# SolderingStation_Processor.net
KiCad netlist of a schematic drawn in Altium Designer
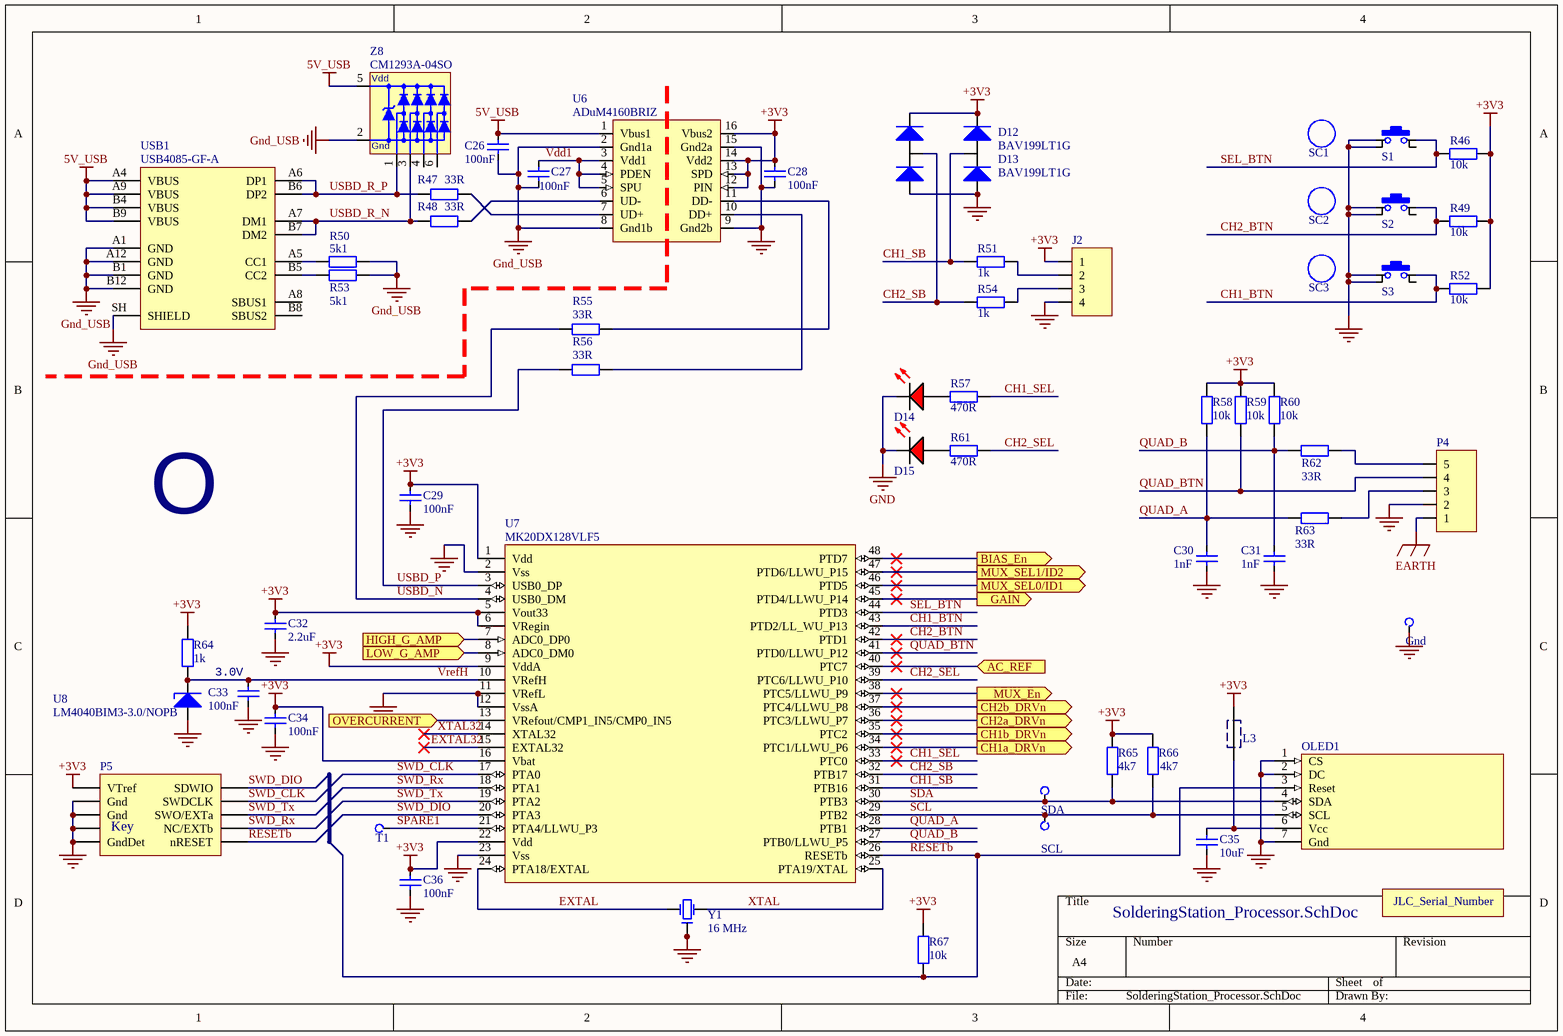
[diagram p0: SolderingStation_Processor.SchDoc]

(export (version "E")
  (design (tool "Eeschema 10.0.6"))
  (components
    (comp (ref "C26")
      (value "100nF")
      (footprint "CCNP1608-0603")
      (description "Capacitor non-polar SMT 0603")
      (fields
        (field (name "MANUFACTURER") "Generic Components")
        (field (name "PUBLISHER") "Altium Hobart Technology Centre")
      )
      (libsource (lib "MyLibrary") (part "Cap_CCNP_0603"))
    )
    (comp (ref "C27")
      (value "100nF")
      (footprint "CCNP1608-0603")
      (description "Capacitor non-polar SMT 0603")
      (fields
        (field (name "MANUFACTURER") "Generic Components")
        (field (name "PUBLISHER") "Altium Hobart Technology Centre")
      )
      (libsource (lib "MyLibrary") (part "Cap_CCNP_0603"))
    )
    (comp (ref "C28")
      (value "100nF")
      (footprint "CCNP1608-0603")
      (description "Capacitor non-polar SMT 0603")
      (fields
        (field (name "MANUFACTURER") "Generic Components")
        (field (name "PUBLISHER") "Altium Hobart Technology Centre")
      )
      (libsource (lib "MyLibrary") (part "Cap_CCNP_0603"))
    )
    (comp (ref "C29")
      (value "100nF")
      (footprint "CCNP1608-0603")
      (description "Capacitor non-polar SMT 0603")
      (fields
        (field (name "MANUFACTURER") "Generic Components")
        (field (name "PUBLISHER") "Altium Hobart Technology Centre")
      )
      (libsource (lib "MyLibrary") (part "Cap_CCNP_0603"))
    )
    (comp (ref "C30")
      (value "1nF")
      (footprint "CCNP1608-0603")
      (description "Capacitor non-polar SMT 0603")
      (fields
        (field (name "MANUFACTURER") "Generic Components")
        (field (name "PUBLISHER") "Altium Hobart Technology Centre")
      )
      (libsource (lib "MyLibrary") (part "Cap_CCNP_0603"))
    )
    (comp (ref "C31")
      (value "1nF")
      (footprint "CCNP1608-0603")
      (description "Capacitor non-polar SMT 0603")
      (fields
        (field (name "MANUFACTURER") "Generic Components")
        (field (name "PUBLISHER") "Altium Hobart Technology Centre")
      )
      (libsource (lib "MyLibrary") (part "Cap_CCNP_0603"))
    )
    (comp (ref "C32")
      (value "2.2uF")
      (footprint "CCNP1608-0603")
      (description "Capacitor")
      (fields
        (field (name "MANUFACTURER") "Generic Components")
        (field (name "PUBLISHER") "Altium Hobart Technology Centre")
      )
      (libsource (lib "MyLibrary") (part "Cap"))
    )
    (comp (ref "C33")
      (value "100nF")
      (footprint "CCNP1608-0603")
      (description "Capacitor non-polar SMT 0603")
      (fields
        (field (name "MANUFACTURER") "Generic Components")
        (field (name "PUBLISHER") "Altium Hobart Technology Centre")
      )
      (libsource (lib "MyLibrary") (part "Cap_CCNP_0603"))
    )
    (comp (ref "C34")
      (value "100nF")
      (footprint "CCNP1608-0603")
      (description "Capacitor non-polar SMT 0603")
      (fields
        (field (name "MANUFACTURER") "Generic Components")
        (field (name "PUBLISHER") "Altium Hobart Technology Centre")
      )
      (libsource (lib "MyLibrary") (part "Cap_CCNP_0603"))
    )
    (comp (ref "C35")
      (value "10uF")
      (footprint "CCNP2012-0805")
      (description "Capacitor")
      (fields
        (field (name "MANUFACTURER") "Generic Components")
        (field (name "PUBLISHER") "Altium Hobart Technology Centre")
      )
      (libsource (lib "MyLibrary") (part "Cap"))
    )
    (comp (ref "C36")
      (value "100nF")
      (footprint "CCNP1608-0603")
      (description "Capacitor non-polar SMT 0603")
      (fields
        (field (name "MANUFACTURER") "Generic Components")
        (field (name "PUBLISHER") "Altium Hobart Technology Centre")
      )
      (libsource (lib "MyLibrary") (part "Cap_CCNP_0603"))
    )
    (comp (ref "D12")
      (value "BAV199LT1G")
      (footprint "SOT23_M")
      (description "Dual Series low-leakage switching diodes, 3-Pin SOT-23")
      (libsource (lib "MySchLib") (part "BAV199LT1G"))
    )
    (comp (ref "D13")
      (value "BAV199LT1G")
      (footprint "SOT23_M")
      (description "Dual Series low-leakage switching diodes, 3-Pin SOT-23")
      (libsource (lib "MySchLib") (part "BAV199LT1G"))
    )
    (comp (ref "D14")
      (value "LED")
      (footprint "LED3MM-RED - 10mm Proud")
      (description "3mm Red LED")
      (fields (field (name "MANUFACTURER") "Generic Components") (field (name "PUBLISHER") "Altium Limited"))
      (libsource (lib "MySchLib") (part "LED_3MM_RED"))
    )
    (comp (ref "D15")
      (value "LED")
      (footprint "LED3MM-RED - 10mm Proud")
      (description "3mm Red LED")
      (fields (field (name "MANUFACTURER") "Generic Components") (field (name "PUBLISHER") "Altium Limited"))
      (libsource (lib "MySchLib") (part "LED_3MM_RED"))
    )
    (comp (ref "Gnd")
      (value "Gnd")
      (footprint "PCBPIN - 0.7mm")
      (description "Test Point")
      (libsource (lib "MySchLib") (part "TP"))
    )
    (comp (ref "J2")
      (value "JST XH Connector, 4-Pin")
      (footprint "jst-b4b-xh-ax")
      (fields (field (name "PUBLISHER") "Altium Limited"))
      (libsource (lib "MyLibrary") (part "JST-B4B-XH-A"))
    )
    (comp (ref "JLC_Serial_Number1")
      (value "JLC_Serial_Number")
      (footprint "JLC_Serial_Number")
      (libsource (lib "MyLibrary") (part "JLC_Serial_Number"))
    )
    (comp (ref "L3")
      (value "Ferrite Bead")
      (footprint "FB2012-0805")
      (description "Ferrite Bead SMT 0805, TDK MPZ2012S102AT, 0.15OHM, 1.5A")
      (libsource (lib "MySchLib") (part "Ferrite Bead 0805"))
    )
    (comp (ref "Logo1")
      (value "OSHW Logo")
      (footprint "OSHW")
      (libsource (lib "MyLibrary") (part "OSHW Logo"))
    )
    (comp (ref "OLED1")
      (value "OLED_Display")
      (footprint "OLED_Display_128x64_2.4inch - no mounting holes")
      (description "OLED Display 128x64 pixels, 2.4inch")
      (libsource (lib "MySchLib") (part "OLED_Display_128x64_2.4inch"))
    )
    (comp (ref "P4")
      (value "Header, 5-Pin")
      (footprint "HDR1X5S")
      (fields (field (name "PUBLISHER") "Altium Limited"))
      (libsource (lib "MyLibrary") (part "Header 1x5"))
    )
    (comp (ref "P5")
      (value "SWD Connector 2x5-Pin")
      (footprint "SWD-2x5-Jig-Header")
      (fields (field (name "PUBLISHER") "Altium Limited"))
      (libsource (lib "MySchLib") (part "SWD2X5_JIG"))
    )
    (comp (ref "R46")
      (value "10k")
      (footprint "CR1608-0603_N")
      (description "Resistor SMT 0603")
      (fields
        (field (name "MANUFACTURER") "Generic Components")
        (field (name "PUBLISHER") "Altium Hobart Technology Centre")
      )
      (libsource (lib "") (part "Res_CR0603_2"))
    )
    (comp (ref "R47")
      (value "33R")
      (footprint "CR1608-0603_N")
      (description "Resistor SMT 0603")
      (fields
        (field (name "MANUFACTURER") "Generic Components")
        (field (name "PUBLISHER") "Altium Hobart Technology Centre")
      )
      (libsource (lib "") (part "Res_CR0603_1"))
    )
    (comp (ref "R48")
      (value "33R")
      (footprint "CR1608-0603_N")
      (description "Resistor SMT 0603")
      (fields
        (field (name "MANUFACTURER") "Generic Components")
        (field (name "PUBLISHER") "Altium Hobart Technology Centre")
      )
      (libsource (lib "") (part "Res_CR0603_1"))
    )
    (comp (ref "R49")
      (value "10k")
      (footprint "CR1608-0603_N")
      (description "Resistor SMT 0603")
      (fields
        (field (name "MANUFACTURER") "Generic Components")
        (field (name "PUBLISHER") "Altium Hobart Technology Centre")
      )
      (libsource (lib "") (part "Res_CR0603_2"))
    )
    (comp (ref "R50")
      (value "5k1")
      (footprint "CR1608-0603_N")
      (description "Resistor SMT 0603")
      (fields
        (field (name "MANUFACTURER") "Generic Components")
        (field (name "PUBLISHER") "Altium Hobart Technology Centre")
      )
      (libsource (lib "") (part "Res_CR0603_2"))
    )
    (comp (ref "R51")
      (value "1k")
      (footprint "CR1608-0603_N")
      (description "Resistor SMT 0603")
      (fields
        (field (name "MANUFACTURER") "Generic Components")
        (field (name "PUBLISHER") "Altium Hobart Technology Centre")
      )
      (libsource (lib "MyLibrary") (part "Res_CR0603"))
    )
    (comp (ref "R52")
      (value "10k")
      (footprint "CR1608-0603_N")
      (description "Resistor SMT 0603")
      (fields
        (field (name "MANUFACTURER") "Generic Components")
        (field (name "PUBLISHER") "Altium Hobart Technology Centre")
      )
      (libsource (lib "") (part "Res_CR0603_2"))
    )
    (comp (ref "R53")
      (value "5k1")
      (footprint "CR1608-0603_N")
      (description "Resistor SMT 0603")
      (fields
        (field (name "MANUFACTURER") "Generic Components")
        (field (name "PUBLISHER") "Altium Hobart Technology Centre")
      )
      (libsource (lib "") (part "Res_CR0603_2"))
    )
    (comp (ref "R54")
      (value "1k")
      (footprint "CR1608-0603_N")
      (description "Resistor SMT 0603")
      (fields
        (field (name "MANUFACTURER") "Generic Components")
        (field (name "PUBLISHER") "Altium Hobart Technology Centre")
      )
      (libsource (lib "MyLibrary") (part "Res_CR0603"))
    )
    (comp (ref "R55")
      (value "33R")
      (footprint "CR1608-0603_N")
      (description "Resistor SMT 0603")
      (fields
        (field (name "MANUFACTURER") "Generic Components")
        (field (name "PUBLISHER") "Altium Hobart Technology Centre")
      )
      (libsource (lib "") (part "Res_CR0603_1"))
    )
    (comp (ref "R56")
      (value "33R")
      (footprint "CR1608-0603_N")
      (description "Resistor SMT 0603")
      (fields
        (field (name "MANUFACTURER") "Generic Components")
        (field (name "PUBLISHER") "Altium Hobart Technology Centre")
      )
      (libsource (lib "") (part "Res_CR0603_1"))
    )
    (comp (ref "R57")
      (value "470R")
      (footprint "CR1608-0603_N")
      (description "Resistor SMT 0603")
      (fields
        (field (name "MANUFACTURER") "Generic Components")
        (field (name "PUBLISHER") "Altium Hobart Technology Centre")
      )
      (libsource (lib "") (part "Res_CR0603_1"))
    )
    (comp (ref "R58")
      (value "10k")
      (footprint "CR1608-0603_N")
      (description "Resistor SMT 0603")
      (fields
        (field (name "MANUFACTURER") "Generic Components")
        (field (name "PUBLISHER") "Altium Hobart Technology Centre")
      )
      (libsource (lib "MyLibrary") (part "Res_CR0603"))
    )
    (comp (ref "R59")
      (value "10k")
      (footprint "CR1608-0603_N")
      (description "Resistor SMT 0603")
      (fields
        (field (name "MANUFACTURER") "Generic Components")
        (field (name "PUBLISHER") "Altium Hobart Technology Centre")
      )
      (libsource (lib "MyLibrary") (part "Res_CR0603"))
    )
    (comp (ref "R60")
      (value "10k")
      (footprint "CR1608-0603_N")
      (description "Resistor SMT 0603")
      (fields
        (field (name "MANUFACTURER") "Generic Components")
        (field (name "PUBLISHER") "Altium Hobart Technology Centre")
      )
      (libsource (lib "MyLibrary") (part "Res_CR0603"))
    )
    (comp (ref "R61")
      (value "470R")
      (footprint "CR1608-0603_N")
      (description "Resistor SMT 0603")
      (fields
        (field (name "MANUFACTURER") "Generic Components")
        (field (name "PUBLISHER") "Altium Hobart Technology Centre")
      )
      (libsource (lib "MyLibrary") (part "Res_CR0603"))
    )
    (comp (ref "R62")
      (value "33R")
      (footprint "CR1608-0603_N")
      (description "Resistor SMT 0603")
      (fields
        (field (name "MANUFACTURER") "Generic Components")
        (field (name "PUBLISHER") "Altium Hobart Technology Centre")
      )
      (libsource (lib "") (part "Res_CR0603_1"))
    )
    (comp (ref "R63")
      (value "33R")
      (footprint "CR1608-0603_N")
      (description "Resistor SMT 0603")
      (fields
        (field (name "MANUFACTURER") "Generic Components")
        (field (name "PUBLISHER") "Altium Hobart Technology Centre")
      )
      (libsource (lib "") (part "Res_CR0603_1"))
    )
    (comp (ref "R64")
      (value "1k")
      (footprint "CR1608-0603_N")
      (description "Resistor SMT 0603")
      (fields
        (field (name "MANUFACTURER") "Generic Components")
        (field (name "PUBLISHER") "Altium Hobart Technology Centre")
      )
      (libsource (lib "") (part "Res_CR0603_1"))
    )
    (comp (ref "R65")
      (value "4k7")
      (footprint "CR1608-0603_N")
      (description "Resistor SMT 0603")
      (fields
        (field (name "MANUFACTURER") "Generic Components")
        (field (name "PUBLISHER") "Altium Hobart Technology Centre")
      )
      (libsource (lib "MyLibrary") (part "Res_CR0603"))
    )
    (comp (ref "R66")
      (value "4k7")
      (footprint "CR1608-0603_N")
      (description "Resistor SMT 0603")
      (fields
        (field (name "MANUFACTURER") "Generic Components")
        (field (name "PUBLISHER") "Altium Hobart Technology Centre")
      )
      (libsource (lib "MyLibrary") (part "Res_CR0603"))
    )
    (comp (ref "R67")
      (value "10k")
      (footprint "CR1608-0603_N")
      (description "Resistor SMT 0603")
      (fields
        (field (name "MANUFACTURER") "Generic Components")
        (field (name "PUBLISHER") "Altium Hobart Technology Centre")
      )
      (libsource (lib "MyLibrary") (part "Res_CR0603"))
    )
    (comp (ref "S1")
      (value "SW_PB-B3F1052")
      (footprint "SW_MIN_PB-B3F1052")
      (description "Switch miniature push-button")
      (fields (field (name "MANUFACTURER") "Generic Components") (field (name "PUBLISHER") "Altium Limited"))
      (libsource (lib "MySchLib") (part "SW_PB-B3F1052"))
    )
    (comp (ref "S2")
      (value "SW_PB-B3F1052")
      (footprint "SW_MIN_PB-B3F1052")
      (description "Switch miniature push-button")
      (fields (field (name "MANUFACTURER") "Generic Components") (field (name "PUBLISHER") "Altium Limited"))
      (libsource (lib "MySchLib") (part "SW_PB-B3F1052"))
    )
    (comp (ref "S3")
      (value "SW_PB-B3F1052")
      (footprint "SW_MIN_PB-B3F1052")
      (description "Switch miniature push-button")
      (fields (field (name "MANUFACTURER") "Generic Components") (field (name "PUBLISHER") "Altium Limited"))
      (libsource (lib "MySchLib") (part "SW_PB-B3F1052"))
    )
    (comp (ref "SC1")
      (value "B32-2010")
      (footprint "SW-CAP-B32-2010")
      (description "Switch Cap")
      (libsource (lib "MySchLib") (part "Switch-Cap - B32-2010"))
    )
    (comp (ref "SC2")
      (value "B32-2010")
      (footprint "SW-CAP-B32-2010")
      (description "Switch Cap")
      (libsource (lib "MySchLib") (part "Switch-Cap - B32-2010"))
    )
    (comp (ref "SC3")
      (value "B32-2010")
      (footprint "SW-CAP-B32-2010")
      (description "Switch Cap")
      (libsource (lib "MySchLib") (part "Switch-Cap - B32-2010"))
    )
    (comp (ref "SCL")
      (value "SCL")
      (footprint "PCBPIN - 0.7mm")
      (description "Test Point")
      (libsource (lib "MySchLib") (part "TP"))
    )
    (comp (ref "SDA")
      (value "SDA")
      (footprint "PCBPIN - 0.7mm")
      (description "Test Point")
      (libsource (lib "MySchLib") (part "TP"))
    )
    (comp (ref "T1")
      (value "PTA4")
      (footprint "PCBPIN - 0.7mm")
      (description "Test Point")
      (libsource (lib "MySchLib") (part "TP"))
    )
    (comp (ref "U6")
      (value "ADuM4160BRIZ")
      (footprint "SOIC127P1030-16M")
      (description "Full/Low Speed 5 kV USB Digital Isolator")
      (libsource (lib "MySchLib") (part "ADuM4160BRIZ"))
    )
    (comp (ref "U7")
      (value "MK20DX128VLF5")
      (footprint "TSQFP50P900X900-48M")
      (description "Kinetis K20: 50MHz Cortex-M4 Performance MCU, 160KB Flash, 16KB SRAM, Full-Speed USB, 48-LQFP")
      (libsource (lib "MySchLib") (part "MK20DX128VLF5"))
    )
    (comp (ref "U8")
      (value "LM4040BIM3-3.0/NOPB")
      (footprint "SOT23_M")
      (description "IC 2.5V VREF SHUNT 0.2% SOT23-3")
      (libsource (lib "MySchLib") (part "LM4040BIM3-2.5/NOPB"))
    )
    (comp (ref "USB1")
      (value "USB4085-GF-A")
      (footprint "USB4085-GF-A")
      (description "USB-C, USB 2.0 Receptacle Connector 16 Position Through Hole, Right Angle")
      (fields (field (name "DIGIKEY PART NUMBER") "2073-USB4085-GF-ACT-ND"))
      (libsource (lib "MyLibrary") (part "USB4085-GF-A"))
    )
    (comp (ref "Y1")
      (value "16 MHz")
      (footprint "Crystal_SMD_3.2x2.5")
      (description "Crystal SMD 3.2 x 2.5 x 0.7 mm")
      (fields
        (field (name "MANUFACTURER") "Generic Components")
        (field (name "PUBLISHER") "Altium Hobart Technology Centre")
      )
      (libsource (lib "MyLibrary") (part "Crystal 16MHz"))
    )
    (comp (ref "Z8")
      (value "CM1293A-04SO")
      (footprint "SOT457_M - 180")
      (description "Ultra low capacitance quadruple rail-to-rail ESD protection")
      (libsource (lib "MySchLib") (part "CM1293A-04SO"))
    )
  )
  (nets
    (net (code "1") (name "+3V3") (class "Default")
      (node (ref "C28") (pin "2") (pinfunction "2_2") (pintype "passive"))
      (node (ref "C29") (pin "2") (pinfunction "2_2") (pintype "passive"))
      (node (ref "C32") (pin "2") (pinfunction "2_2") (pintype "passive"))
      (node (ref "C34") (pin "2") (pinfunction "2_2") (pintype "passive"))
      (node (ref "C36") (pin "2") (pinfunction "2_2") (pintype "passive"))
      (node (ref "D12") (pin "2") (pinfunction "A2_2") (pintype "passive"))
      (node (ref "D13") (pin "2") (pinfunction "A2_2") (pintype "passive"))
      (node (ref "J2") (pin "1") (pinfunction "1_1") (pintype "passive"))
      (node (ref "L3") (pin "1") (pinfunction "1_1") (pintype "passive"))
      (node (ref "P5") (pin "1") (pinfunction "VTref_1") (pintype "passive"))
      (node (ref "R46") (pin "2") (pinfunction "2_2") (pintype "passive"))
      (node (ref "R49") (pin "2") (pinfunction "2_2") (pintype "passive"))
      (node (ref "R52") (pin "2") (pinfunction "2_2") (pintype "passive"))
      (node (ref "R58") (pin "2") (pinfunction "2_2") (pintype "passive"))
      (node (ref "R59") (pin "2") (pinfunction "2_2") (pintype "passive"))
      (node (ref "R60") (pin "2") (pinfunction "2_2") (pintype "passive"))
      (node (ref "R64") (pin "1") (pinfunction "1_1") (pintype "passive"))
      (node (ref "R65") (pin "2") (pinfunction "2_2") (pintype "passive"))
      (node (ref "R66") (pin "2") (pinfunction "2_2") (pintype "passive"))
      (node (ref "R67") (pin "2") (pinfunction "2_2") (pintype "passive"))
      (node (ref "U6") (pin "12") (pinfunction "PIN_12") (pintype "input"))
      (node (ref "U6") (pin "13") (pinfunction "SPD_13") (pintype "input"))
      (node (ref "U6") (pin "14") (pinfunction "Vdd2_14") (pintype "power_in"))
      (node (ref "U6") (pin "16") (pinfunction "Vbus2_16") (pintype "power_in"))
      (node (ref "U7") (pin "1") (pinfunction "Vdd_1") (pintype "power_in"))
      (node (ref "U7") (pin "16") (pinfunction "Vbat_16") (pintype "passive"))
      (node (ref "U7") (pin "22") (pinfunction "Vdd_22") (pintype "power_in"))
      (node (ref "U7") (pin "5") (pinfunction "Vout33_5") (pintype "power_in"))
      (node (ref "U7") (pin "6") (pinfunction "VRegin_6") (pintype "passive"))
      (node (ref "U7") (pin "9") (pinfunction "VddA_9") (pintype "power_in"))
    )
    (net (code "2") (name "/AC_REF") (class "Default")
      (node (ref "U7") (pin "40") (pinfunction "PTC7_40") (pintype "bidirectional"))
    )
    (net (code "3") (name "/BIAS_En") (class "Default")
      (node (ref "U7") (pin "48") (pinfunction "PTD7_48") (pintype "bidirectional"))
    )
    (net (code "4") (name "/CH1_BTN") (class "Default")
      (node (ref "R52") (pin "1") (pinfunction "1_1") (pintype "passive"))
      (node (ref "S3") (pin "2") (pinfunction "2_2") (pintype "passive"))
      (node (ref "U7") (pin "43") (pinfunction "PTD2/LL_WU_P13_43") (pintype "bidirectional"))
    )
    (net (code "5") (name "/CH1_SB") (class "Default")
      (node (ref "D13") (pin "3") (pinfunction "K_3") (pintype "passive"))
      (node (ref "R51") (pin "1") (pinfunction "1_1") (pintype "passive"))
      (node (ref "U7") (pin "31") (pinfunction "PTB16_31") (pintype "bidirectional"))
    )
    (net (code "6") (name "/CH1_SEL") (class "Default")
      (node (ref "R57") (pin "1") (pinfunction "1_1") (pintype "passive"))
      (node (ref "U7") (pin "33") (pinfunction "PTC0_33") (pintype "bidirectional"))
    )
    (net (code "7") (name "/CH1a_DRVn") (class "Default")
      (node (ref "U7") (pin "34") (pinfunction "PTC1/LLWU_P6_34") (pintype "bidirectional"))
    )
    (net (code "8") (name "/CH1b_DRVn") (class "Default")
      (node (ref "U7") (pin "35") (pinfunction "PTC2_35") (pintype "bidirectional"))
    )
    (net (code "9") (name "/CH2_BTN") (class "Default")
      (node (ref "R49") (pin "1") (pinfunction "1_1") (pintype "passive"))
      (node (ref "S2") (pin "2") (pinfunction "2_2") (pintype "passive"))
      (node (ref "U7") (pin "42") (pinfunction "PTD1_42") (pintype "bidirectional"))
    )
    (net (code "10") (name "/CH2_SB") (class "Default")
      (node (ref "D12") (pin "3") (pinfunction "K_3") (pintype "passive"))
      (node (ref "R54") (pin "1") (pinfunction "1_1") (pintype "passive"))
      (node (ref "U7") (pin "32") (pinfunction "PTB17_32") (pintype "bidirectional"))
    )
    (net (code "11") (name "/CH2_SEL") (class "Default")
      (node (ref "R61") (pin "2") (pinfunction "2_2") (pintype "passive"))
      (node (ref "U7") (pin "39") (pinfunction "PTC6/LLWU_P10_39") (pintype "bidirectional"))
    )
    (net (code "12") (name "/CH2a_DRVn") (class "Default")
      (node (ref "U7") (pin "36") (pinfunction "PTC3/LLWU_P7_36") (pintype "bidirectional"))
    )
    (net (code "13") (name "/CH2b_DRVn") (class "Default")
      (node (ref "U7") (pin "37") (pinfunction "PTC4/LLWU_P8_37") (pintype "bidirectional"))
    )
    (net (code "14") (name "/EXTAL") (class "Default")
      (node (ref "U7") (pin "24") (pinfunction "PTA18/EXTAL_24") (pintype "bidirectional"))
      (node (ref "Y1") (pin "3") (pinfunction "OSC2_3") (pintype "passive"))
    )
    (net (code "15") (name "/EXTAL32") (class "Default")
      (node (ref "U7") (pin "15") (pinfunction "EXTAL32_15") (pintype "passive+no_connect"))
    )
    (net (code "16") (name "/GAIN") (class "Default")
      (node (ref "U7") (pin "45") (pinfunction "PTD4/LLWU_P14_45") (pintype "bidirectional"))
    )
    (net (code "17") (name "/HIGH_G_AMP") (class "Default")
      (node (ref "U7") (pin "7") (pinfunction "ADC0_DP0_7") (pintype "input"))
    )
    (net (code "18") (name "/LOW_G_AMP") (class "Default")
      (node (ref "U7") (pin "8") (pinfunction "ADC0_DM0_8") (pintype "input"))
    )
    (net (code "19") (name "/MUX_En") (class "Default")
      (node (ref "U7") (pin "38") (pinfunction "PTC5/LLWU_P9_38") (pintype "bidirectional"))
    )
    (net (code "20") (name "/MUX_SEL0{slash}ID1") (class "Default")
      (node (ref "U7") (pin "46") (pinfunction "PTD5_46") (pintype "bidirectional"))
    )
    (net (code "21") (name "/MUX_SEL1{slash}ID2") (class "Default")
      (node (ref "U7") (pin "47") (pinfunction "PTD6/LLWU_P15_47") (pintype "bidirectional"))
    )
    (net (code "22") (name "/OVERCURRENT") (class "Default")
      (node (ref "U7") (pin "13") (pinfunction "VRefout/CMP1_IN5/CMP0_IN5_13") (pintype "passive"))
    )
    (net (code "23") (name "/QUAD_A") (class "Default")
      (node (ref "C30") (pin "2") (pinfunction "2_2") (pintype "passive"))
      (node (ref "R58") (pin "1") (pinfunction "1_1") (pintype "passive"))
      (node (ref "R63") (pin "2") (pinfunction "2_2") (pintype "passive"))
      (node (ref "U7") (pin "28") (pinfunction "PTB1_28") (pintype "bidirectional"))
    )
    (net (code "24") (name "/QUAD_B") (class "Default")
      (node (ref "C31") (pin "2") (pinfunction "2_2") (pintype "passive"))
      (node (ref "R60") (pin "1") (pinfunction "1_1") (pintype "passive"))
      (node (ref "R62") (pin "2") (pinfunction "2_2") (pintype "passive"))
      (node (ref "U7") (pin "27") (pinfunction "PTB0/LLWU_P5_27") (pintype "bidirectional"))
    )
    (net (code "25") (name "/QUAD_BTN") (class "Default")
      (node (ref "P4") (pin "4") (pinfunction "4_4") (pintype "passive"))
      (node (ref "R59") (pin "1") (pinfunction "1_1") (pintype "passive"))
      (node (ref "U7") (pin "41") (pinfunction "PTD0/LLWU_P12_41") (pintype "bidirectional"))
    )
    (net (code "26") (name "/RESETb") (class "Default")
      (node (ref "OLED1") (pin "3") (pinfunction "Reset_3") (pintype "input"))
      (node (ref "P5") (pin "10") (pinfunction "nRESET_10") (pintype "passive"))
      (node (ref "R67") (pin "1") (pinfunction "1_1") (pintype "passive"))
      (node (ref "U7") (pin "26") (pinfunction "RESETb_26") (pintype "bidirectional"))
    )
    (net (code "27") (name "/SCL") (class "Default")
      (node (ref "OLED1") (pin "5") (pinfunction "SCL_5") (pintype "bidirectional"))
      (node (ref "R66") (pin "1") (pinfunction "1_1") (pintype "passive"))
      (node (ref "SCL") (pin "1") (pinfunction "TP_1") (pintype "passive"))
      (node (ref "U7") (pin "29") (pinfunction "PTB2_29") (pintype "bidirectional"))
    )
    (net (code "28") (name "/SDA") (class "Default")
      (node (ref "OLED1") (pin "4") (pinfunction "SDA_4") (pintype "bidirectional"))
      (node (ref "R65") (pin "1") (pinfunction "1_1") (pintype "passive"))
      (node (ref "SDA") (pin "1") (pinfunction "TP_1") (pintype "passive"))
      (node (ref "U7") (pin "30") (pinfunction "PTB3_30") (pintype "bidirectional"))
    )
    (net (code "29") (name "/SEL_BTN") (class "Default")
      (node (ref "R46") (pin "1") (pinfunction "1_1") (pintype "passive"))
      (node (ref "S1") (pin "2") (pinfunction "2_2") (pintype "passive"))
      (node (ref "U7") (pin "44") (pinfunction "PTD3_44") (pintype "bidirectional"))
    )
    (net (code "30") (name "/SPARE1") (class "Default")
      (node (ref "T1") (pin "1") (pinfunction "TP_1") (pintype "passive"))
      (node (ref "U7") (pin "21") (pinfunction "PTA4/LLWU_P3_21") (pintype "bidirectional"))
    )
    (net (code "31") (name "/SWD_CLK") (class "Default")
      (node (ref "P5") (pin "4") (pinfunction "SWDCLK_4") (pintype "passive"))
      (node (ref "U7") (pin "17") (pinfunction "PTA0_17") (pintype "bidirectional"))
    )
    (net (code "32") (name "/SWD_DIO") (class "Default")
      (node (ref "P5") (pin "2") (pinfunction "SDWIO_2") (pintype "passive"))
      (node (ref "U7") (pin "20") (pinfunction "PTA3_20") (pintype "bidirectional"))
    )
    (net (code "33") (name "/SWD_Rx") (class "Default")
      (node (ref "P5") (pin "8") (pinfunction "NC/EXTb_8") (pintype "passive"))
      (node (ref "U7") (pin "18") (pinfunction "PTA1_18") (pintype "bidirectional"))
    )
    (net (code "34") (name "/SWD_Tx") (class "Default")
      (node (ref "P5") (pin "6") (pinfunction "SWO/EXTa_6") (pintype "passive"))
      (node (ref "U7") (pin "19") (pinfunction "PTA2_19") (pintype "bidirectional"))
    )
    (net (code "35") (name "/USBD_N") (class "Default")
      (node (ref "R55") (pin "2") (pinfunction "2_2") (pintype "passive"))
      (node (ref "U7") (pin "4") (pinfunction "USB0_DM_4") (pintype "bidirectional"))
    )
    (net (code "36") (name "/USBD_P") (class "Default")
      (node (ref "R56") (pin "2") (pinfunction "2_2") (pintype "passive"))
      (node (ref "U7") (pin "3") (pinfunction "USB0_DP_3") (pintype "bidirectional"))
    )
    (net (code "37") (name "/USBD_R_N") (class "Default")
      (node (ref "R48") (pin "2") (pinfunction "2_2") (pintype "passive"))
      (node (ref "USB1") (pin "A7") (pinfunction "DM1_A7") (pintype "passive"))
      (node (ref "USB1") (pin "B7") (pinfunction "DM2_B7") (pintype "passive"))
      (node (ref "Z8") (pin "3") (pintype "passive"))
    )
    (net (code "38") (name "/USBD_R_P") (class "Default")
      (node (ref "R47") (pin "2") (pinfunction "2_2") (pintype "passive"))
      (node (ref "USB1") (pin "A6") (pinfunction "DP1_A6") (pintype "passive"))
      (node (ref "USB1") (pin "B6") (pinfunction "DP2_B6") (pintype "passive"))
      (node (ref "Z8") (pin "1") (pintype "passive"))
    )
    (net (code "39") (name "/Vdd1") (class "Default")
      (node (ref "C27") (pin "2") (pinfunction "2_2") (pintype "passive"))
      (node (ref "U6") (pin "3") (pinfunction "Vdd1_3") (pintype "power_in"))
      (node (ref "U6") (pin "4") (pinfunction "PDEN_4") (pintype "input"))
      (node (ref "U6") (pin "5") (pinfunction "SPU_5") (pintype "input"))
    )
    (net (code "40") (name "/VrefH") (class "Default")
      (node (ref "C33") (pin "2") (pinfunction "2_2") (pintype "passive"))
      (node (ref "R64") (pin "2") (pinfunction "2_2") (pintype "passive"))
      (node (ref "U7") (pin "10") (pinfunction "VRefH_10") (pintype "passive"))
      (node (ref "U8") (pin "1") (pinfunction "K_1") (pintype "passive"))
    )
    (net (code "41") (name "/XTAL") (class "Default")
      (node (ref "U7") (pin "25") (pinfunction "PTA19/XTAL_25") (pintype "bidirectional"))
      (node (ref "Y1") (pin "1") (pinfunction "OSC1_1") (pintype "passive"))
    )
    (net (code "42") (name "/XTAL32") (class "Default")
      (node (ref "U7") (pin "14") (pinfunction "XTAL32_14") (pintype "passive+no_connect"))
    )
    (net (code "43") (name "5V_USB") (class "Default")
      (node (ref "C26") (pin "2") (pinfunction "2_2") (pintype "passive"))
      (node (ref "U6") (pin "1") (pinfunction "Vbus1_1") (pintype "power_in"))
      (node (ref "USB1") (pin "A4") (pinfunction "VBUS_A4") (pintype "passive"))
      (node (ref "USB1") (pin "A9") (pinfunction "VBUS_A9") (pintype "passive"))
      (node (ref "USB1") (pin "B4") (pinfunction "VBUS_B4") (pintype "passive"))
      (node (ref "USB1") (pin "B9") (pinfunction "VBUS_B9") (pintype "passive"))
      (node (ref "Z8") (pin "5") (pinfunction "Vp_5") (pintype "passive"))
    )
    (net (code "44") (name "EARTH") (class "Default")
      (node (ref "P4") (pin "1") (pinfunction "1_1") (pintype "passive"))
    )
    (net (code "45") (name "GND") (class "Default")
      (node (ref "C28") (pin "1") (pinfunction "1_1") (pintype "passive"))
      (node (ref "C29") (pin "1") (pinfunction "1_1") (pintype "passive"))
      (node (ref "C30") (pin "1") (pinfunction "1_1") (pintype "passive"))
      (node (ref "C31") (pin "1") (pinfunction "1_1") (pintype "passive"))
      (node (ref "C32") (pin "1") (pinfunction "1_1") (pintype "passive"))
      (node (ref "C33") (pin "1") (pinfunction "1_1") (pintype "passive"))
      (node (ref "C34") (pin "1") (pinfunction "1_1") (pintype "passive"))
      (node (ref "C35") (pin "1") (pinfunction "1_1") (pintype "passive"))
      (node (ref "C36") (pin "1") (pinfunction "1_1") (pintype "passive"))
      (node (ref "D12") (pin "1") (pinfunction "A1_1") (pintype "passive"))
      (node (ref "D13") (pin "1") (pinfunction "A1_1") (pintype "passive"))
      (node (ref "D14") (pin "K") (pinfunction "K_K") (pintype "passive"))
      (node (ref "D15") (pin "K") (pinfunction "K_K") (pintype "passive"))
      (node (ref "Gnd") (pin "1") (pinfunction "TP_1") (pintype "passive"))
      (node (ref "J2") (pin "4") (pinfunction "4_4") (pintype "passive"))
      (node (ref "OLED1") (pin "1") (pinfunction "CS_1") (pintype "input"))
      (node (ref "OLED1") (pin "2") (pinfunction "DC_2") (pintype "input"))
      (node (ref "OLED1") (pin "7") (pinfunction "Gnd_7") (pintype "power_in"))
      (node (ref "P4") (pin "2") (pinfunction "2_2") (pintype "passive"))
      (node (ref "P5") (pin "0") (pinfunction "Pins_0") (pintype "power_in"))
      (node (ref "P5") (pin "3") (pinfunction "Gnd_3") (pintype "passive"))
      (node (ref "P5") (pin "5") (pinfunction "Gnd_5") (pintype "passive"))
      (node (ref "P5") (pin "9") (pinfunction "GndDet_9") (pintype "passive"))
      (node (ref "S1") (pin "1") (pinfunction "1_1") (pintype "passive"))
      (node (ref "S1") (pin "1b") (pinfunction "1b_1b") (pintype "passive"))
      (node (ref "S2") (pin "1") (pinfunction "1_1") (pintype "passive"))
      (node (ref "S2") (pin "1b") (pinfunction "1b_1b") (pintype "passive"))
      (node (ref "S3") (pin "1") (pinfunction "1_1") (pintype "passive"))
      (node (ref "S3") (pin "1b") (pinfunction "1b_1b") (pintype "passive"))
      (node (ref "U6") (pin "15") (pinfunction "Gnd2a_15") (pintype "power_in"))
      (node (ref "U6") (pin "9") (pinfunction "Gnd2b_9") (pintype "power_in"))
      (node (ref "U7") (pin "11") (pinfunction "VRefL_11") (pintype "passive"))
      (node (ref "U7") (pin "12") (pinfunction "VssA_12") (pintype "power_in"))
      (node (ref "U7") (pin "2") (pinfunction "Vss_2") (pintype "power_in"))
      (node (ref "U7") (pin "23") (pinfunction "Vss_23") (pintype "power_in"))
      (node (ref "U8") (pin "2") (pinfunction "A_2") (pintype "passive"))
      (node (ref "Y1") (pin "2") (pinfunction "Gnd_2") (pintype "passive"))
      (node (ref "Y1") (pin "4") (pinfunction "Gnd_4") (pintype "passive"))
    )
    (net (code "46") (name "Gnd_USB") (class "Default")
      (node (ref "C26") (pin "1") (pinfunction "1_1") (pintype "passive"))
      (node (ref "C27") (pin "1") (pinfunction "1_1") (pintype "passive"))
      (node (ref "R50") (pin "2") (pinfunction "2_2") (pintype "passive"))
      (node (ref "R53") (pin "2") (pinfunction "2_2") (pintype "passive"))
      (node (ref "U6") (pin "2") (pinfunction "Gnd1a_2") (pintype "power_in"))
      (node (ref "U6") (pin "8") (pinfunction "Gnd1b_8") (pintype "power_in"))
      (node (ref "USB1") (pin "A1") (pinfunction "GND_A1") (pintype "passive"))
      (node (ref "USB1") (pin "A12") (pinfunction "GND_A12") (pintype "passive"))
      (node (ref "USB1") (pin "B1") (pinfunction "GND_B1") (pintype "passive"))
      (node (ref "USB1") (pin "B12") (pinfunction "GND_B12") (pintype "passive"))
      (node (ref "USB1") (pin "SH") (pinfunction "SHIELD_SH") (pintype "passive"))
      (node (ref "Z8") (pin "2") (pinfunction "Vn_2") (pintype "passive"))
    )
    (net (code "47") (name "Net-(D14-PadA)") (class "Default")
      (node (ref "D14") (pin "A") (pinfunction "A_A") (pintype "passive"))
      (node (ref "R57") (pin "2") (pinfunction "2_2") (pintype "passive"))
    )
    (net (code "48") (name "Net-(D15-PadA)") (class "Default")
      (node (ref "D15") (pin "A") (pinfunction "A_A") (pintype "passive"))
      (node (ref "R61") (pin "1") (pinfunction "1_1") (pintype "passive"))
    )
    (net (code "49") (name "Net-(J2-Pad2)") (class "Default")
      (node (ref "J2") (pin "2") (pinfunction "2_2") (pintype "passive"))
      (node (ref "R51") (pin "2") (pinfunction "2_2") (pintype "passive"))
    )
    (net (code "50") (name "Net-(J2-Pad3)") (class "Default")
      (node (ref "J2") (pin "3") (pinfunction "3_3") (pintype "passive"))
      (node (ref "R54") (pin "2") (pinfunction "2_2") (pintype "passive"))
    )
    (net (code "51") (name "Net-(OLED1-Vcc)") (class "Default")
      (node (ref "C35") (pin "2") (pinfunction "2_2") (pintype "passive"))
      (node (ref "L3") (pin "2") (pinfunction "2_2") (pintype "passive"))
      (node (ref "OLED1") (pin "6") (pinfunction "Vcc_6") (pintype "power_in"))
    )
    (net (code "52") (name "Net-(P4-Pad3)") (class "Default")
      (node (ref "P4") (pin "3") (pinfunction "3_3") (pintype "passive"))
      (node (ref "R63") (pin "1") (pinfunction "1_1") (pintype "passive"))
    )
    (net (code "53") (name "Net-(P4-Pad5)") (class "Default")
      (node (ref "P4") (pin "5") (pinfunction "5_5") (pintype "passive"))
      (node (ref "R62") (pin "1") (pinfunction "1_1") (pintype "passive"))
    )
    (net (code "54") (name "Net-(U6-DD+)") (class "Default")
      (node (ref "R56") (pin "1") (pinfunction "1_1") (pintype "passive"))
      (node (ref "U6") (pin "10") (pinfunction "DD+_10") (pintype "bidirectional"))
    )
    (net (code "55") (name "Net-(U6-DD-)") (class "Default")
      (node (ref "R55") (pin "1") (pinfunction "1_1") (pintype "passive"))
      (node (ref "U6") (pin "11") (pinfunction "DD-_11") (pintype "bidirectional"))
    )
    (net (code "56") (name "Net-(U6-UD+)") (class "Default")
      (node (ref "R47") (pin "1") (pinfunction "1_1") (pintype "passive"))
      (node (ref "U6") (pin "7") (pinfunction "UD+_7") (pintype "bidirectional"))
    )
    (net (code "57") (name "Net-(U6-UD-)") (class "Default")
      (node (ref "R48") (pin "1") (pinfunction "1_1") (pintype "passive"))
      (node (ref "U6") (pin "6") (pinfunction "UD-_6") (pintype "bidirectional"))
    )
    (net (code "58") (name "Net-(USB1-CC1)") (class "Default")
      (node (ref "R50") (pin "1") (pinfunction "1_1") (pintype "passive"))
      (node (ref "USB1") (pin "A5") (pinfunction "CC1_A5") (pintype "passive"))
    )
    (net (code "59") (name "Net-(USB1-CC2)") (class "Default")
      (node (ref "R53") (pin "1") (pinfunction "1_1") (pintype "passive"))
      (node (ref "USB1") (pin "B5") (pinfunction "CC2_B5") (pintype "passive"))
    )
    (net (code "60") (name "unconnected-(S1-Pad2b)") (class "Default")
      (node (ref "S1") (pin "2b") (pinfunction "2b_2b") (pintype "passive"))
    )
    (net (code "61") (name "unconnected-(S2-Pad2b)") (class "Default")
      (node (ref "S2") (pin "2b") (pinfunction "2b_2b") (pintype "passive"))
    )
    (net (code "62") (name "unconnected-(S3-Pad2b)") (class "Default")
      (node (ref "S3") (pin "2b") (pinfunction "2b_2b") (pintype "passive"))
    )
    (net (code "63") (name "unconnected-(U8-NC-Pad3)") (class "Default")
      (node (ref "U8") (pin "3") (pinfunction "NC_3") (pintype "passive"))
    )
    (net (code "64") (name "unconnected-(USB1-SBUS1-PadA8)") (class "Default")
      (node (ref "USB1") (pin "A8") (pinfunction "SBUS1_A8") (pintype "passive"))
    )
    (net (code "65") (name "unconnected-(USB1-SBUS2-PadB8)") (class "Default")
      (node (ref "USB1") (pin "B8") (pinfunction "SBUS2_B8") (pintype "passive"))
    )
    (net (code "66") (name "unconnected-(Z8-Pad4)") (class "Default")
      (node (ref "Z8") (pin "4") (pintype "passive"))
    )
    (net (code "67") (name "unconnected-(Z8-Pad6)") (class "Default")
      (node (ref "Z8") (pin "6") (pintype "passive"))
    )
  )
)
